# xmas_id_badge_0_12.net
KiCad netlist of a schematic drawn in EAGLE
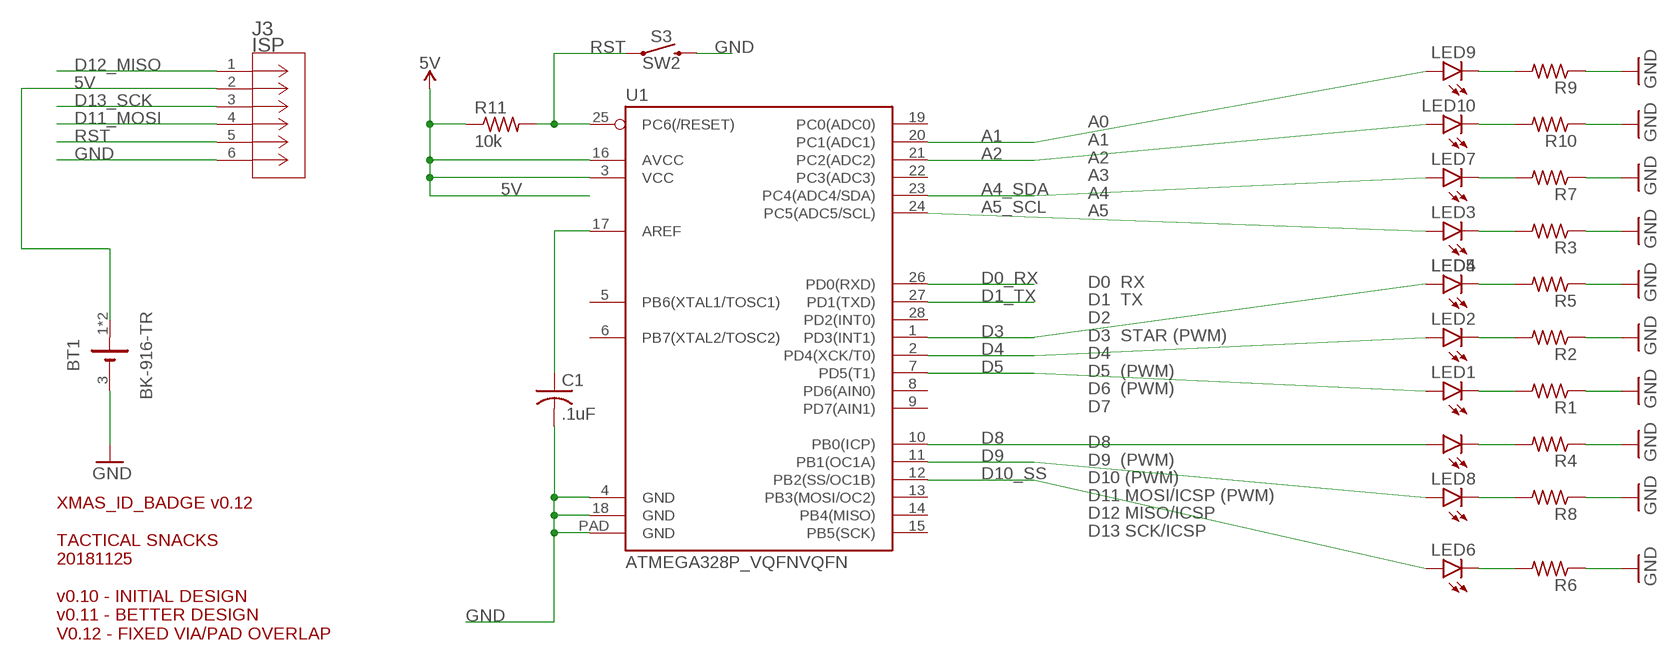
[diagram p0: schematic, sheet 1]

(export (version "E")
  (design (tool "Eeschema 10.0.6"))
  (components
    (comp (ref "BT1")
      (value "BK-916-TR")
      (footprint "eagle-import:BAT_BK-916-TR")
      (fields (field (name "DIGI-KEY_PART_NUMBER") "BK-916-CT-ND") (field (name "MF") "MPD _Memory"))
      (libsource (lib "eagle-import") (part "BK-916-TR"))
    )
    (comp (ref "C1")
      (value ".1uF")
      (footprint "eagle-import:C0603")
      (libsource (lib "eagle-import") (part "C-USC0603"))
    )
    (comp (ref "J3")
      (value "ISP")
      (footprint "eagle-import:CON6_2X3_DU_FTSH-L_REV")
      (libsource (lib "eagle-import") (part "FTSH-103-01-F-DVCON6_2X3_DU_FTSH-L_REV"))
    )
    (comp (ref "LED1")
      (value "LEDCHIP-LED0805")
      (footprint "eagle-import:CHIP-LED0805")
      (libsource (lib "eagle-import") (part "LEDCHIP-LED0805"))
    )
    (comp (ref "LED2")
      (value "LEDCHIP-LED0805")
      (footprint "eagle-import:CHIP-LED0805")
      (libsource (lib "eagle-import") (part "LEDCHIP-LED0805"))
    )
    (comp (ref "LED3")
      (value "LEDCHIP-LED0805")
      (footprint "eagle-import:CHIP-LED0805")
      (libsource (lib "eagle-import") (part "LEDCHIP-LED0805"))
    )
    (comp (ref "LED4")
      (value "LEDCHIP-LED0805")
      (footprint "eagle-import:CHIP-LED0805")
      (libsource (lib "eagle-import") (part "LEDCHIP-LED0805"))
    )
    (comp (ref "LED5")
      (value "LEDCHIP-LED0805")
      (footprint "eagle-import:CHIP-LED0805")
      (libsource (lib "eagle-import") (part "LEDCHIP-LED0805"))
    )
    (comp (ref "LED6")
      (value "LEDCHIP-LED0805")
      (footprint "eagle-import:CHIP-LED0805")
      (libsource (lib "eagle-import") (part "LEDCHIP-LED0805"))
    )
    (comp (ref "LED7")
      (value "LEDCHIP-LED0805")
      (footprint "eagle-import:CHIP-LED0805")
      (libsource (lib "eagle-import") (part "LEDCHIP-LED0805"))
    )
    (comp (ref "LED8")
      (value "LEDCHIP-LED0805")
      (footprint "eagle-import:CHIP-LED0805")
      (libsource (lib "eagle-import") (part "LEDCHIP-LED0805"))
    )
    (comp (ref "LED9")
      (value "LEDCHIP-LED0805")
      (footprint "eagle-import:CHIP-LED0805")
      (libsource (lib "eagle-import") (part "LEDCHIP-LED0805"))
    )
    (comp (ref "LED10")
      (value "LEDCHIP-LED0805")
      (footprint "eagle-import:CHIP-LED0805")
      (libsource (lib "eagle-import") (part "LEDCHIP-LED0805"))
    )
    (comp (ref "R1")
      (value "R-US_R0603")
      (footprint "eagle-import:R0603")
      (libsource (lib "eagle-import") (part "rcl_334_R-US_R0603"))
    )
    (comp (ref "R2")
      (value "R-US_R0603")
      (footprint "eagle-import:R0603")
      (libsource (lib "eagle-import") (part "rcl_334_R-US_R0603"))
    )
    (comp (ref "R3")
      (value "R-US_R0603")
      (footprint "eagle-import:R0603")
      (libsource (lib "eagle-import") (part "rcl_334_R-US_R0603"))
    )
    (comp (ref "R4")
      (value "R-US_R0603")
      (footprint "eagle-import:R0603")
      (libsource (lib "eagle-import") (part "rcl_334_R-US_R0603"))
    )
    (comp (ref "R5")
      (value "R-US_R0603")
      (footprint "eagle-import:R0603")
      (libsource (lib "eagle-import") (part "rcl_334_R-US_R0603"))
    )
    (comp (ref "R6")
      (value "R-US_R0603")
      (footprint "eagle-import:R0603")
      (libsource (lib "eagle-import") (part "rcl_334_R-US_R0603"))
    )
    (comp (ref "R7")
      (value "R-US_R0603")
      (footprint "eagle-import:R0603")
      (libsource (lib "eagle-import") (part "rcl_334_R-US_R0603"))
    )
    (comp (ref "R8")
      (value "R-US_R0603")
      (footprint "eagle-import:R0603")
      (libsource (lib "eagle-import") (part "rcl_334_R-US_R0603"))
    )
    (comp (ref "R9")
      (value "R-US_R0603")
      (footprint "eagle-import:R0603")
      (libsource (lib "eagle-import") (part "rcl_334_R-US_R0603"))
    )
    (comp (ref "R10")
      (value "R-US_R0603")
      (footprint "eagle-import:R0603")
      (libsource (lib "eagle-import") (part "rcl_334_R-US_R0603"))
    )
    (comp (ref "R11")
      (value "10k")
      (footprint "eagle-import:R0805")
      (libsource (lib "eagle-import") (part "R-US_R0805"))
    )
    (comp (ref "S3")
      (value "SW2")
      (footprint "eagle-import:TACTILE_SWITCH_SMD_6.0X3.5MM")
      (libsource (lib "eagle-import") (part "MOMENTARY-SWITCH-SPST-SMD-6.0X3.5MM"))
    )
    (comp (ref "U1")
      (value "ATMEGA328P_VQFNVQFN")
      (footprint "eagle-import:VQFN-28")
      (libsource (lib "eagle-import") (part "ATMEGA328P_VQFNVQFN"))
    )
  )
  (nets
    (net (code "1") (name "/A1") (class "Default")
      (node (ref "LED9") (pin "A") (pinfunction "A_A") (pintype "passive"))
      (node (ref "U1") (pin "20") (pinfunction "PC1(ADC1)_20") (pintype "bidirectional"))
    )
    (net (code "2") (name "/A2") (class "Default")
      (node (ref "LED10") (pin "A") (pinfunction "A_A") (pintype "passive"))
      (node (ref "U1") (pin "21") (pinfunction "PC2(ADC2)_21") (pintype "bidirectional"))
    )
    (net (code "3") (name "/A4_SDA") (class "Default")
      (node (ref "LED7") (pin "A") (pinfunction "A_A") (pintype "passive"))
      (node (ref "U1") (pin "23") (pinfunction "PC4(ADC4/SDA)_23") (pintype "bidirectional"))
    )
    (net (code "4") (name "/A5_SCL") (class "Default")
      (node (ref "LED3") (pin "A") (pinfunction "A_A") (pintype "passive"))
      (node (ref "U1") (pin "24") (pinfunction "PC5(ADC5/SCL)_24") (pintype "bidirectional"))
    )
    (net (code "5") (name "/D0_RX") (class "Default")
      (node (ref "U1") (pin "26") (pinfunction "PD0(RXD)_26") (pintype "bidirectional"))
    )
    (net (code "6") (name "/D1_TX") (class "Default")
      (node (ref "U1") (pin "27") (pinfunction "PD1(TXD)_27") (pintype "bidirectional"))
    )
    (net (code "7") (name "/D3") (class "Default")
      (node (ref "LED5") (pin "A") (pinfunction "A_A") (pintype "passive"))
      (node (ref "U1") (pin "1") (pinfunction "PD3(INT1)_1") (pintype "bidirectional"))
    )
    (net (code "8") (name "/D4") (class "Default")
      (node (ref "LED2") (pin "A") (pinfunction "A_A") (pintype "passive"))
      (node (ref "U1") (pin "2") (pinfunction "PD4(XCK/T0)_2") (pintype "bidirectional"))
    )
    (net (code "9") (name "/D5") (class "Default")
      (node (ref "LED1") (pin "A") (pinfunction "A_A") (pintype "passive"))
      (node (ref "U1") (pin "7") (pinfunction "PD5(T1)_7") (pintype "bidirectional"))
    )
    (net (code "10") (name "/D8") (class "Default")
      (node (ref "LED4") (pin "A") (pinfunction "A_A") (pintype "passive"))
      (node (ref "U1") (pin "10") (pinfunction "PB0(ICP)_10") (pintype "bidirectional"))
    )
    (net (code "11") (name "/D9") (class "Default")
      (node (ref "LED8") (pin "A") (pinfunction "A_A") (pintype "passive"))
      (node (ref "U1") (pin "11") (pinfunction "PB1(OC1A)_11") (pintype "bidirectional"))
    )
    (net (code "12") (name "/D10_SS") (class "Default")
      (node (ref "LED6") (pin "A") (pinfunction "A_A") (pintype "passive"))
      (node (ref "U1") (pin "12") (pinfunction "PB2(SS/OC1B)_12") (pintype "bidirectional"))
    )
    (net (code "13") (name "/D11_MOSI") (class "Default")
      (node (ref "J3") (pin "4") (pinfunction "4_4") (pintype "passive"))
    )
    (net (code "14") (name "/D12_MISO") (class "Default")
      (node (ref "J3") (pin "1") (pinfunction "1_1") (pintype "passive"))
    )
    (net (code "15") (name "/D13_SCK") (class "Default")
      (node (ref "J3") (pin "3") (pinfunction "3_3") (pintype "passive"))
    )
    (net (code "16") (name "/RST") (class "Default")
      (node (ref "J3") (pin "5") (pinfunction "5_5") (pintype "passive"))
      (node (ref "R11") (pin "2") (pinfunction "2_2") (pintype "passive"))
      (node (ref "S3") (pin "1") (pinfunction "1_1") (pintype "passive"))
      (node (ref "U1") (pin "25") (pinfunction "PC6(/RESET)_25") (pintype "bidirectional"))
    )
    (net (code "17") (name "5V") (class "Default")
      (node (ref "BT1") (pin "1") (pinfunction "+_1") (pintype "passive"))
      (node (ref "BT1") (pin "2") (pinfunction "+_2") (pintype "passive"))
      (node (ref "J3") (pin "2") (pinfunction "2_2") (pintype "passive"))
      (node (ref "R11") (pin "1") (pinfunction "1_1") (pintype "passive"))
      (node (ref "U1") (pin "16") (pinfunction "AVCC_16") (pintype "bidirectional"))
      (node (ref "U1") (pin "3") (pinfunction "VCC_3") (pintype "bidirectional"))
    )
    (net (code "18") (name "GND") (class "Default")
      (node (ref "BT1") (pin "3") (pinfunction "-_3") (pintype "passive"))
      (node (ref "C1") (pin "2") (pinfunction "2_2") (pintype "passive"))
      (node (ref "J3") (pin "6") (pinfunction "6_6") (pintype "passive"))
      (node (ref "R1") (pin "1") (pinfunction "1_1") (pintype "passive"))
      (node (ref "R10") (pin "1") (pinfunction "1_1") (pintype "passive"))
      (node (ref "R2") (pin "1") (pinfunction "1_1") (pintype "passive"))
      (node (ref "R3") (pin "1") (pinfunction "1_1") (pintype "passive"))
      (node (ref "R4") (pin "1") (pinfunction "1_1") (pintype "passive"))
      (node (ref "R5") (pin "1") (pinfunction "1_1") (pintype "passive"))
      (node (ref "R6") (pin "1") (pinfunction "1_1") (pintype "passive"))
      (node (ref "R7") (pin "1") (pinfunction "1_1") (pintype "passive"))
      (node (ref "R8") (pin "1") (pinfunction "1_1") (pintype "passive"))
      (node (ref "R9") (pin "1") (pinfunction "1_1") (pintype "passive"))
      (node (ref "S3") (pin "2") (pinfunction "2_2") (pintype "passive"))
      (node (ref "U1") (pin "18") (pinfunction "GND_18") (pintype "bidirectional"))
      (node (ref "U1") (pin "4") (pinfunction "GND_4") (pintype "bidirectional"))
      (node (ref "U1") (pin "PAD") (pinfunction "GND_PAD") (pintype "bidirectional"))
    )
    (net (code "19") (name "Net-(LED1-PadC)") (class "Default")
      (node (ref "LED1") (pin "C") (pinfunction "C_C") (pintype "passive"))
      (node (ref "R1") (pin "2") (pinfunction "2_2") (pintype "passive"))
    )
    (net (code "20") (name "Net-(LED2-PadC)") (class "Default")
      (node (ref "LED2") (pin "C") (pinfunction "C_C") (pintype "passive"))
      (node (ref "R2") (pin "2") (pinfunction "2_2") (pintype "passive"))
    )
    (net (code "21") (name "Net-(LED3-PadC)") (class "Default")
      (node (ref "LED3") (pin "C") (pinfunction "C_C") (pintype "passive"))
      (node (ref "R3") (pin "2") (pinfunction "2_2") (pintype "passive"))
    )
    (net (code "22") (name "Net-(LED4-PadC)") (class "Default")
      (node (ref "LED4") (pin "C") (pinfunction "C_C") (pintype "passive"))
      (node (ref "R4") (pin "2") (pinfunction "2_2") (pintype "passive"))
    )
    (net (code "23") (name "Net-(LED5-PadC)") (class "Default")
      (node (ref "LED5") (pin "C") (pinfunction "C_C") (pintype "passive"))
      (node (ref "R5") (pin "2") (pinfunction "2_2") (pintype "passive"))
    )
    (net (code "24") (name "Net-(LED6-PadC)") (class "Default")
      (node (ref "LED6") (pin "C") (pinfunction "C_C") (pintype "passive"))
      (node (ref "R6") (pin "2") (pinfunction "2_2") (pintype "passive"))
    )
    (net (code "25") (name "Net-(LED7-PadC)") (class "Default")
      (node (ref "LED7") (pin "C") (pinfunction "C_C") (pintype "passive"))
      (node (ref "R7") (pin "2") (pinfunction "2_2") (pintype "passive"))
    )
    (net (code "26") (name "Net-(LED8-PadC)") (class "Default")
      (node (ref "LED8") (pin "C") (pinfunction "C_C") (pintype "passive"))
      (node (ref "R8") (pin "2") (pinfunction "2_2") (pintype "passive"))
    )
    (net (code "27") (name "Net-(LED9-PadC)") (class "Default")
      (node (ref "LED9") (pin "C") (pinfunction "C_C") (pintype "passive"))
      (node (ref "R9") (pin "2") (pinfunction "2_2") (pintype "passive"))
    )
    (net (code "28") (name "Net-(LED10-PadC)") (class "Default")
      (node (ref "LED10") (pin "C") (pinfunction "C_C") (pintype "passive"))
      (node (ref "R10") (pin "2") (pinfunction "2_2") (pintype "passive"))
    )
    (net (code "29") (name "Net-(U1-AREF)") (class "Default")
      (node (ref "C1") (pin "1") (pinfunction "1_1") (pintype "passive"))
      (node (ref "U1") (pin "17") (pinfunction "AREF_17") (pintype "bidirectional"))
    )
    (net (code "30") (name "unconnected-(U1-PB3(MOSI{slash}OC2)-Pad13)") (class "Default")
      (node (ref "U1") (pin "13") (pinfunction "PB3(MOSI/OC2)_13") (pintype "bidirectional"))
    )
    (net (code "31") (name "unconnected-(U1-PB4(MISO)-Pad14)") (class "Default")
      (node (ref "U1") (pin "14") (pinfunction "PB4(MISO)_14") (pintype "bidirectional"))
    )
    (net (code "32") (name "unconnected-(U1-PB5(SCK)-Pad15)") (class "Default")
      (node (ref "U1") (pin "15") (pinfunction "PB5(SCK)_15") (pintype "bidirectional"))
    )
    (net (code "33") (name "unconnected-(U1-PB6(XTAL1{slash}TOSC1)-Pad5)") (class "Default")
      (node (ref "U1") (pin "5") (pinfunction "PB6(XTAL1/TOSC1)_5") (pintype "bidirectional"))
    )
    (net (code "34") (name "unconnected-(U1-PB7(XTAL2{slash}TOSC2)-Pad6)") (class "Default")
      (node (ref "U1") (pin "6") (pinfunction "PB7(XTAL2/TOSC2)_6") (pintype "bidirectional"))
    )
    (net (code "35") (name "unconnected-(U1-PC0(ADC0)-Pad19)") (class "Default")
      (node (ref "U1") (pin "19") (pinfunction "PC0(ADC0)_19") (pintype "bidirectional"))
    )
    (net (code "36") (name "unconnected-(U1-PC3(ADC3)-Pad22)") (class "Default")
      (node (ref "U1") (pin "22") (pinfunction "PC3(ADC3)_22") (pintype "bidirectional"))
    )
    (net (code "37") (name "unconnected-(U1-PD2(INT0)-Pad28)") (class "Default")
      (node (ref "U1") (pin "28") (pinfunction "PD2(INT0)_28") (pintype "bidirectional"))
    )
    (net (code "38") (name "unconnected-(U1-PD6(AIN0)-Pad8)") (class "Default")
      (node (ref "U1") (pin "8") (pinfunction "PD6(AIN0)_8") (pintype "bidirectional"))
    )
    (net (code "39") (name "unconnected-(U1-PD7(AIN1)-Pad9)") (class "Default")
      (node (ref "U1") (pin "9") (pinfunction "PD7(AIN1)_9") (pintype "bidirectional"))
    )
  )
)
